# pypl.net
KiCad netlist of a schematic drawn in EAGLE
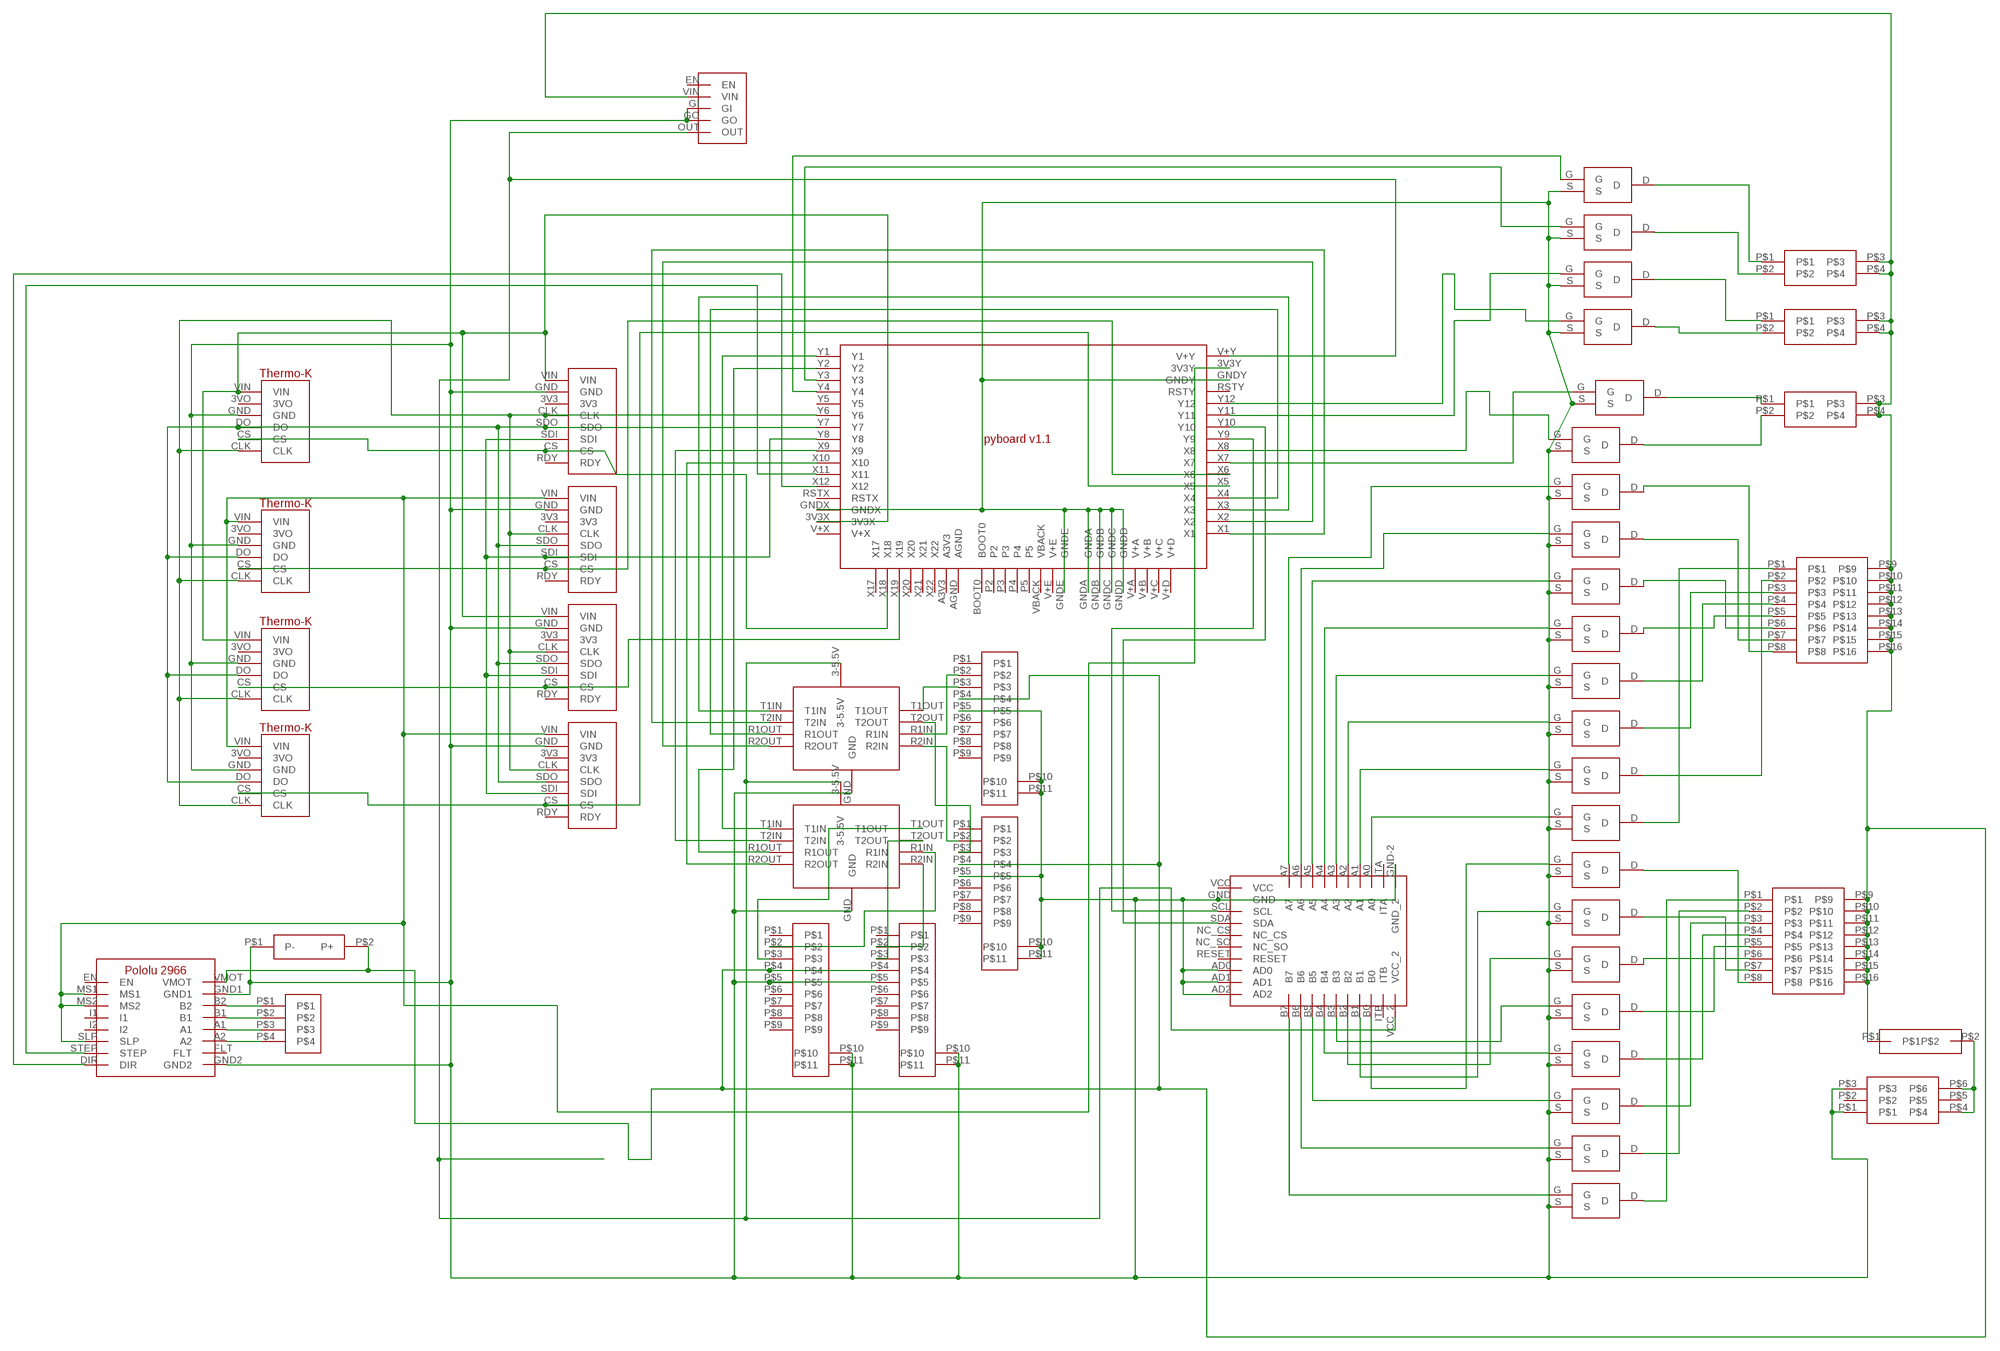
[diagram p0: schematic, sheet 1]

(export (version "E")
  (design (tool "Eeschema 10.0.6"))
  (components
    (comp (ref "U$1")
      (value "MAX31865")
      (footprint "eagle-import:MAX31865")
      (libsource (lib "eagle-import") (part "MAX31865"))
    )
    (comp (ref "U$2")
      (value "IRLB8721PBF")
      (footprint "eagle-import:IRLB8721PBF")
      (libsource (lib "eagle-import") (part "IRLB8721PBF"))
    )
    (comp (ref "U$3")
      (value "IRLB8721PBF")
      (footprint "eagle-import:IRLB8721PBF")
      (libsource (lib "eagle-import") (part "IRLB8721PBF"))
    )
    (comp (ref "U$4")
      (value "IRLB8721PBF")
      (footprint "eagle-import:IRLB8721PBF")
      (libsource (lib "eagle-import") (part "IRLB8721PBF"))
    )
    (comp (ref "U$5")
      (value "IRLB8721PBF")
      (footprint "eagle-import:IRLB8721PBF")
      (libsource (lib "eagle-import") (part "IRLB8721PBF"))
    )
    (comp (ref "U$6")
      (value "IRLB8721PBF")
      (footprint "eagle-import:IRLB8721PBF")
      (libsource (lib "eagle-import") (part "IRLB8721PBF"))
    )
    (comp (ref "U$7")
      (value "IRLB8721PBF")
      (footprint "eagle-import:IRLB8721PBF")
      (libsource (lib "eagle-import") (part "IRLB8721PBF"))
    )
    (comp (ref "U$8")
      (value "IRLB8721PBF")
      (footprint "eagle-import:IRLB8721PBF")
      (libsource (lib "eagle-import") (part "IRLB8721PBF"))
    )
    (comp (ref "U$9")
      (value "IRLB8721PBF")
      (footprint "eagle-import:IRLB8721PBF")
      (libsource (lib "eagle-import") (part "IRLB8721PBF"))
    )
    (comp (ref "U$10")
      (value "MCP23017")
      (footprint "eagle-import:MCP23017")
      (libsource (lib "eagle-import") (part "MCP23017"))
    )
    (comp (ref "U$11")
      (value "IRLB8721PBF")
      (footprint "eagle-import:IRLB8721PBF")
      (libsource (lib "eagle-import") (part "IRLB8721PBF"))
    )
    (comp (ref "U$12")
      (value "IRLB8721PBF")
      (footprint "eagle-import:IRLB8721PBF")
      (libsource (lib "eagle-import") (part "IRLB8721PBF"))
    )
    (comp (ref "U$13")
      (value "IRLB8721PBF")
      (footprint "eagle-import:IRLB8721PBF")
      (libsource (lib "eagle-import") (part "IRLB8721PBF"))
    )
    (comp (ref "U$14")
      (value "IRLB8721PBF")
      (footprint "eagle-import:IRLB8721PBF")
      (libsource (lib "eagle-import") (part "IRLB8721PBF"))
    )
    (comp (ref "U$15")
      (value "IRLB8721PBF")
      (footprint "eagle-import:IRLB8721PBF")
      (libsource (lib "eagle-import") (part "IRLB8721PBF"))
    )
    (comp (ref "U$16")
      (value "IRLB8721PBF")
      (footprint "eagle-import:IRLB8721PBF")
      (libsource (lib "eagle-import") (part "IRLB8721PBF"))
    )
    (comp (ref "U$17")
      (value "IRLB8721PBF")
      (footprint "eagle-import:IRLB8721PBF")
      (libsource (lib "eagle-import") (part "IRLB8721PBF"))
    )
    (comp (ref "U$18")
      (value "IRLB8721PBF")
      (footprint "eagle-import:IRLB8721PBF")
      (libsource (lib "eagle-import") (part "IRLB8721PBF"))
    )
    (comp (ref "U$19")
      (value "DSUB-9")
      (footprint "eagle-import:DSUB-9")
      (libsource (lib "eagle-import") (part "DSUB-9"))
    )
    (comp (ref "U$20")
      (value "DSUB-9")
      (footprint "eagle-import:DSUB-9")
      (libsource (lib "eagle-import") (part "DSUB-9"))
    )
    (comp (ref "U$21")
      (value "DSUB-9")
      (footprint "eagle-import:DSUB-9")
      (libsource (lib "eagle-import") (part "DSUB-9"))
    )
    (comp (ref "U$22")
      (value "DSUB-9")
      (footprint "eagle-import:DSUB-9")
      (libsource (lib "eagle-import") (part "DSUB-9"))
    )
    (comp (ref "U$23")
      (value "MAX31865")
      (footprint "eagle-import:MAX31865")
      (libsource (lib "eagle-import") (part "MAX31865"))
    )
    (comp (ref "U$24")
      (value "PYBOARD_V1.1")
      (footprint "eagle-import:PYBOARD_V1.1")
      (libsource (lib "eagle-import") (part "PYBOARD_V1.1"))
    )
    (comp (ref "U$25")
      (value "MAX31865")
      (footprint "eagle-import:MAX31865")
      (libsource (lib "eagle-import") (part "MAX31865"))
    )
    (comp (ref "U$26")
      (value "MAX31865")
      (footprint "eagle-import:MAX31865")
      (libsource (lib "eagle-import") (part "MAX31865"))
    )
    (comp (ref "U$27")
      (value "BORNIER_DUPLEX_X16")
      (footprint "eagle-import:BORNIER_DUPLEX_X16")
      (libsource (lib "eagle-import") (part "BORNIER_DUPLEX_X16"))
    )
    (comp (ref "U$28")
      (value "BORNIER_DUPLEX_X16")
      (footprint "eagle-import:BORNIER_DUPLEX_X16")
      (libsource (lib "eagle-import") (part "BORNIER_DUPLEX_X16"))
    )
    (comp (ref "U$29")
      (value "CAP-GOTRONIC-04936")
      (footprint "eagle-import:CAP-GOTRONIC-04936")
      (libsource (lib "eagle-import") (part "CAP-GOTRONIC-04936"))
    )
    (comp (ref "U$30")
      (value "BORNIER_1X4_2.54")
      (footprint "eagle-import:BORNIER_1X4_2.54")
      (libsource (lib "eagle-import") (part "BORNIER_1X4_2.54"))
    )
    (comp (ref "U$31")
      (value "PORTE-FUSIBLE")
      (footprint "eagle-import:PORTE-FUSIBLE")
      (libsource (lib "eagle-import") (part "PORTE-FUSIBLE"))
    )
    (comp (ref "U$32")
      (value "MP6500-2966")
      (footprint "eagle-import:MP6500-2966")
      (libsource (lib "eagle-import") (part "MP6500-2966"))
    )
    (comp (ref "U$33")
      (value "IRLB8721PBF")
      (footprint "eagle-import:IRLB8721PBF")
      (libsource (lib "eagle-import") (part "IRLB8721PBF"))
    )
    (comp (ref "U$34")
      (value "IRLB8721PBF")
      (footprint "eagle-import:IRLB8721PBF")
      (libsource (lib "eagle-import") (part "IRLB8721PBF"))
    )
    (comp (ref "U$35")
      (value "BORNIER_DUPLEX_X4")
      (footprint "eagle-import:BORNIER_DUPLEX_X4")
      (libsource (lib "eagle-import") (part "BORNIER_DUPLEX_X4"))
    )
    (comp (ref "U$36")
      (value "BOB-1189")
      (footprint "eagle-import:BOB-11189")
      (libsource (lib "eagle-import") (part "BOB-1189"))
    )
    (comp (ref "U$37")
      (value "BOB-1189")
      (footprint "eagle-import:BOB-11189")
      (libsource (lib "eagle-import") (part "BOB-1189"))
    )
    (comp (ref "U$38")
      (value "MOLEX_MINIFT_JR_ANGLED_X6")
      (footprint "eagle-import:MOLEX_MINIFT_JR_ANGLED_X6")
      (libsource (lib "eagle-import") (part "MOLEX_MINIFT_JR_ANGLED_X6"))
    )
    (comp (ref "U$39")
      (value "D24V50F5D24V50F5")
      (footprint "eagle-import:D24V50F5")
      (libsource (lib "eagle-import") (part "D24V50F5D24V50F5"))
    )
    (comp (ref "U$40")
      (value "BORNIER_DUPLEX_X4")
      (footprint "eagle-import:BORNIER_DUPLEX_X4")
      (libsource (lib "eagle-import") (part "BORNIER_DUPLEX_X4"))
    )
    (comp (ref "U$41")
      (value "BORNIER_DUPLEX_X4")
      (footprint "eagle-import:BORNIER_DUPLEX_X4")
      (libsource (lib "eagle-import") (part "BORNIER_DUPLEX_X4"))
    )
    (comp (ref "U$42")
      (value "IRLB8721PBF")
      (footprint "eagle-import:IRLB8721PBF")
      (libsource (lib "eagle-import") (part "IRLB8721PBF"))
    )
    (comp (ref "U$43")
      (value "IRLB8721PBF")
      (footprint "eagle-import:IRLB8721PBF")
      (libsource (lib "eagle-import") (part "IRLB8721PBF"))
    )
    (comp (ref "U$44")
      (value "IRLB8721PBF")
      (footprint "eagle-import:IRLB8721PBF")
      (libsource (lib "eagle-import") (part "IRLB8721PBF"))
    )
    (comp (ref "U$45")
      (value "IRLB8721PBF")
      (footprint "eagle-import:IRLB8721PBF")
      (libsource (lib "eagle-import") (part "IRLB8721PBF"))
    )
    (comp (ref "U$46")
      (value "MAX31855")
      (footprint "eagle-import:MAX31855")
      (libsource (lib "eagle-import") (part "MAX31855"))
    )
    (comp (ref "U$47")
      (value "MAX31855")
      (footprint "eagle-import:MAX31855")
      (libsource (lib "eagle-import") (part "MAX31855"))
    )
    (comp (ref "U$48")
      (value "MAX31855")
      (footprint "eagle-import:MAX31855")
      (libsource (lib "eagle-import") (part "MAX31855"))
    )
    (comp (ref "U$49")
      (value "MAX31855")
      (footprint "eagle-import:MAX31855")
      (libsource (lib "eagle-import") (part "MAX31855"))
    )
  )
  (nets
    (net (code "1") (name "Net-(U$1-PadCLK)") (class "Default")
      (node (ref "U$1") (pin "CLK") (pinfunction "CLK_CLK") (pintype "bidirectional"))
      (node (ref "U$23") (pin "CLK") (pinfunction "CLK_CLK") (pintype "bidirectional"))
      (node (ref "U$24") (pin "Y6") (pinfunction "Y6_Y6") (pintype "bidirectional"))
      (node (ref "U$25") (pin "CLK") (pinfunction "CLK_CLK") (pintype "bidirectional"))
      (node (ref "U$26") (pin "CLK") (pinfunction "CLK_CLK") (pintype "bidirectional"))
      (node (ref "U$46") (pin "CLK") (pinfunction "CLK_CLK") (pintype "bidirectional"))
      (node (ref "U$47") (pin "CLK") (pinfunction "CLK_CLK") (pintype "bidirectional"))
      (node (ref "U$48") (pin "CLK") (pinfunction "CLK_CLK") (pintype "bidirectional"))
      (node (ref "U$49") (pin "CLK") (pinfunction "CLK_CLK") (pintype "bidirectional"))
    )
    (net (code "2") (name "Net-(U$1-PadCS)") (class "Default")
      (node (ref "U$1") (pin "CS") (pinfunction "CS_CS") (pintype "bidirectional"))
      (node (ref "U$24") (pin "X19") (pinfunction "X19_X19") (pintype "bidirectional"))
      (node (ref "U$48") (pin "CS") (pinfunction "CS_CS") (pintype "bidirectional"))
    )
    (net (code "3") (name "Net-(U$1-PadSDI)") (class "Default")
      (node (ref "U$1") (pin "SDI") (pinfunction "SDI_SDI") (pintype "bidirectional"))
      (node (ref "U$23") (pin "SDI") (pinfunction "SDI_SDI") (pintype "bidirectional"))
      (node (ref "U$24") (pin "Y8") (pinfunction "Y8_Y8") (pintype "bidirectional"))
      (node (ref "U$25") (pin "SDI") (pinfunction "SDI_SDI") (pintype "bidirectional"))
      (node (ref "U$26") (pin "SDI") (pinfunction "SDI_SDI") (pintype "bidirectional"))
    )
    (net (code "4") (name "Net-(U$1-PadSDO)") (class "Default")
      (node (ref "U$1") (pin "SDO") (pinfunction "SDO_SDO") (pintype "bidirectional"))
      (node (ref "U$23") (pin "SDO") (pinfunction "SDO_SDO") (pintype "bidirectional"))
      (node (ref "U$24") (pin "Y7") (pinfunction "Y7_Y7") (pintype "bidirectional"))
      (node (ref "U$25") (pin "SDO") (pinfunction "SDO_SDO") (pintype "bidirectional"))
      (node (ref "U$26") (pin "SDO") (pinfunction "SDO_SDO") (pintype "bidirectional"))
      (node (ref "U$46") (pin "DO") (pinfunction "DO_DO") (pintype "bidirectional"))
      (node (ref "U$47") (pin "DO") (pinfunction "DO_DO") (pintype "bidirectional"))
      (node (ref "U$48") (pin "DO") (pinfunction "DO_DO") (pintype "bidirectional"))
      (node (ref "U$49") (pin "DO") (pinfunction "DO_DO") (pintype "bidirectional"))
    )
    (net (code "5") (name "Net-(U$1-PadVIN)") (class "Default")
      (node (ref "U$1") (pin "VIN") (pinfunction "VIN_VIN") (pintype "bidirectional"))
      (node (ref "U$24") (pin "3V3X") (pinfunction "3V3X_3V3X") (pintype "bidirectional"))
      (node (ref "U$25") (pin "VIN") (pinfunction "VIN_VIN") (pintype "bidirectional"))
      (node (ref "U$46") (pin "VIN") (pinfunction "VIN_VIN") (pintype "bidirectional"))
      (node (ref "U$48") (pin "VIN") (pinfunction "VIN_VIN") (pintype "bidirectional"))
    )
    (net (code "6") (name "Net-(U$2-PadD)") (class "Default")
      (node (ref "U$2") (pin "D") (pinfunction "D_D") (pintype "bidirectional"))
      (node (ref "U$28") (pin "P$3") (pinfunction "P$3_P$3") (pintype "bidirectional"))
    )
    (net (code "7") (name "Net-(U$10-GND_2)") (class "Default")
      (node (ref "U$1") (pin "GND") (pinfunction "GND_GND") (pintype "bidirectional"))
      (node (ref "U$10") (pin "AD0") (pinfunction "AD0_AD0") (pintype "bidirectional"))
      (node (ref "U$10") (pin "AD1") (pinfunction "AD1_AD1") (pintype "bidirectional"))
      (node (ref "U$10") (pin "AD2") (pinfunction "AD2_AD2") (pintype "bidirectional"))
      (node (ref "U$10") (pin "GND") (pinfunction "GND_GND") (pintype "bidirectional"))
      (node (ref "U$10") (pin "GND-2") (pinfunction "GND_2_GND-2") (pintype "bidirectional"))
      (node (ref "U$11") (pin "S") (pinfunction "S_S") (pintype "bidirectional"))
      (node (ref "U$12") (pin "S") (pinfunction "S_S") (pintype "bidirectional"))
      (node (ref "U$13") (pin "S") (pinfunction "S_S") (pintype "bidirectional"))
      (node (ref "U$14") (pin "S") (pinfunction "S_S") (pintype "bidirectional"))
      (node (ref "U$15") (pin "S") (pinfunction "S_S") (pintype "bidirectional"))
      (node (ref "U$16") (pin "S") (pinfunction "S_S") (pintype "bidirectional"))
      (node (ref "U$17") (pin "S") (pinfunction "S_S") (pintype "bidirectional"))
      (node (ref "U$18") (pin "S") (pinfunction "S_S") (pintype "bidirectional"))
      (node (ref "U$19") (pin "P$10") (pinfunction "P$10_P$10") (pintype "bidirectional"))
      (node (ref "U$19") (pin "P$11") (pinfunction "P$11_P$11") (pintype "bidirectional"))
      (node (ref "U$19") (pin "P$5") (pinfunction "P$5_P$5") (pintype "bidirectional"))
      (node (ref "U$2") (pin "S") (pinfunction "S_S") (pintype "bidirectional"))
      (node (ref "U$20") (pin "P$10") (pinfunction "P$10_P$10") (pintype "bidirectional"))
      (node (ref "U$20") (pin "P$11") (pinfunction "P$11_P$11") (pintype "bidirectional"))
      (node (ref "U$20") (pin "P$5") (pinfunction "P$5_P$5") (pintype "bidirectional"))
      (node (ref "U$21") (pin "P$10") (pinfunction "P$10_P$10") (pintype "bidirectional"))
      (node (ref "U$21") (pin "P$11") (pinfunction "P$11_P$11") (pintype "bidirectional"))
      (node (ref "U$21") (pin "P$5") (pinfunction "P$5_P$5") (pintype "bidirectional"))
      (node (ref "U$22") (pin "P$10") (pinfunction "P$10_P$10") (pintype "bidirectional"))
      (node (ref "U$22") (pin "P$11") (pinfunction "P$11_P$11") (pintype "bidirectional"))
      (node (ref "U$22") (pin "P$5") (pinfunction "P$5_P$5") (pintype "bidirectional"))
      (node (ref "U$23") (pin "GND") (pinfunction "GND_GND") (pintype "bidirectional"))
      (node (ref "U$24") (pin "GNDA") (pinfunction "GNDA_GNDA") (pintype "bidirectional"))
      (node (ref "U$24") (pin "GNDB") (pinfunction "GNDB_GNDB") (pintype "bidirectional"))
      (node (ref "U$24") (pin "GNDC") (pinfunction "GNDC_GNDC") (pintype "bidirectional"))
      (node (ref "U$24") (pin "GNDD") (pinfunction "GNDD_GNDD") (pintype "bidirectional"))
      (node (ref "U$24") (pin "GNDE") (pinfunction "GNDE_GNDE") (pintype "bidirectional"))
      (node (ref "U$24") (pin "GNDX") (pinfunction "GNDX_GNDX") (pintype "bidirectional"))
      (node (ref "U$24") (pin "GNDY") (pinfunction "GNDY_GNDY") (pintype "bidirectional"))
      (node (ref "U$25") (pin "GND") (pinfunction "GND_GND") (pintype "bidirectional"))
      (node (ref "U$26") (pin "GND") (pinfunction "GND_GND") (pintype "bidirectional"))
      (node (ref "U$29") (pin "P$1") (pinfunction "P-_P$1") (pintype "bidirectional"))
      (node (ref "U$3") (pin "S") (pinfunction "S_S") (pintype "bidirectional"))
      (node (ref "U$32") (pin "GND1") (pinfunction "GND1_GND1") (pintype "bidirectional"))
      (node (ref "U$32") (pin "GND2") (pinfunction "GND2_GND2") (pintype "bidirectional"))
      (node (ref "U$33") (pin "S") (pinfunction "S_S") (pintype "bidirectional"))
      (node (ref "U$34") (pin "S") (pinfunction "S_S") (pintype "bidirectional"))
      (node (ref "U$36") (pin "GND") (pinfunction "GND_GND") (pintype "bidirectional"))
      (node (ref "U$37") (pin "GND") (pinfunction "GND_GND") (pintype "bidirectional"))
      (node (ref "U$38") (pin "P$1") (pinfunction "P$1_P$1") (pintype "bidirectional"))
      (node (ref "U$38") (pin "P$3") (pinfunction "P$3_P$3") (pintype "bidirectional"))
      (node (ref "U$39") (pin "GI") (pinfunction "GI_GI") (pintype "bidirectional"))
      (node (ref "U$39") (pin "GO") (pinfunction "GO_GO") (pintype "bidirectional"))
      (node (ref "U$4") (pin "S") (pinfunction "S_S") (pintype "bidirectional"))
      (node (ref "U$42") (pin "S") (pinfunction "S_S") (pintype "bidirectional"))
      (node (ref "U$43") (pin "S") (pinfunction "S_S") (pintype "bidirectional"))
      (node (ref "U$44") (pin "S") (pinfunction "S_S") (pintype "bidirectional"))
      (node (ref "U$45") (pin "S") (pinfunction "S_S") (pintype "bidirectional"))
      (node (ref "U$46") (pin "GND") (pinfunction "GND_GND") (pintype "bidirectional"))
      (node (ref "U$47") (pin "GND") (pinfunction "GND_GND") (pintype "bidirectional"))
      (node (ref "U$48") (pin "GND") (pinfunction "GND_GND") (pintype "bidirectional"))
      (node (ref "U$49") (pin "GND") (pinfunction "GND_GND") (pintype "bidirectional"))
      (node (ref "U$5") (pin "S") (pinfunction "S_S") (pintype "bidirectional"))
      (node (ref "U$6") (pin "S") (pinfunction "S_S") (pintype "bidirectional"))
      (node (ref "U$7") (pin "S") (pinfunction "S_S") (pintype "bidirectional"))
      (node (ref "U$8") (pin "S") (pinfunction "S_S") (pintype "bidirectional"))
      (node (ref "U$9") (pin "S") (pinfunction "S_S") (pintype "bidirectional"))
    )
    (net (code "8") (name "Net-(U$10-PadA0)") (class "Default")
      (node (ref "U$10") (pin "A0") (pinfunction "A0_A0") (pintype "bidirectional"))
      (node (ref "U$9") (pin "G") (pinfunction "G_G") (pintype "bidirectional"))
    )
    (net (code "9") (name "Net-(U$10-PadA1)") (class "Default")
      (node (ref "U$10") (pin "A1") (pinfunction "A1_A1") (pintype "bidirectional"))
      (node (ref "U$8") (pin "G") (pinfunction "G_G") (pintype "bidirectional"))
    )
    (net (code "10") (name "Net-(U$10-PadA2)") (class "Default")
      (node (ref "U$10") (pin "A2") (pinfunction "A2_A2") (pintype "bidirectional"))
      (node (ref "U$2") (pin "G") (pinfunction "G_G") (pintype "bidirectional"))
    )
    (net (code "11") (name "Net-(U$10-PadA3)") (class "Default")
      (node (ref "U$10") (pin "A3") (pinfunction "A3_A3") (pintype "bidirectional"))
      (node (ref "U$3") (pin "G") (pinfunction "G_G") (pintype "bidirectional"))
    )
    (net (code "12") (name "Net-(U$10-PadA4)") (class "Default")
      (node (ref "U$10") (pin "A4") (pinfunction "A4_A4") (pintype "bidirectional"))
      (node (ref "U$4") (pin "G") (pinfunction "G_G") (pintype "bidirectional"))
    )
    (net (code "13") (name "Net-(U$10-PadA5)") (class "Default")
      (node (ref "U$10") (pin "A5") (pinfunction "A5_A5") (pintype "bidirectional"))
      (node (ref "U$5") (pin "G") (pinfunction "G_G") (pintype "bidirectional"))
    )
    (net (code "14") (name "Net-(U$10-PadA6)") (class "Default")
      (node (ref "U$10") (pin "A6") (pinfunction "A6_A6") (pintype "bidirectional"))
      (node (ref "U$6") (pin "G") (pinfunction "G_G") (pintype "bidirectional"))
    )
    (net (code "15") (name "Net-(U$10-PadA7)") (class "Default")
      (node (ref "U$10") (pin "A7") (pinfunction "A7_A7") (pintype "bidirectional"))
      (node (ref "U$7") (pin "G") (pinfunction "G_G") (pintype "bidirectional"))
    )
    (net (code "16") (name "Net-(U$10-PadB0)") (class "Default")
      (node (ref "U$10") (pin "B0") (pinfunction "B0_B0") (pintype "bidirectional"))
      (node (ref "U$16") (pin "G") (pinfunction "G_G") (pintype "bidirectional"))
    )
    (net (code "17") (name "Net-(U$10-PadB1)") (class "Default")
      (node (ref "U$10") (pin "B1") (pinfunction "B1_B1") (pintype "bidirectional"))
      (node (ref "U$15") (pin "G") (pinfunction "G_G") (pintype "bidirectional"))
    )
    (net (code "18") (name "Net-(U$10-PadB2)") (class "Default")
      (node (ref "U$10") (pin "B2") (pinfunction "B2_B2") (pintype "bidirectional"))
      (node (ref "U$14") (pin "G") (pinfunction "G_G") (pintype "bidirectional"))
    )
    (net (code "19") (name "Net-(U$10-PadB3)") (class "Default")
      (node (ref "U$10") (pin "B3") (pinfunction "B3_B3") (pintype "bidirectional"))
      (node (ref "U$13") (pin "G") (pinfunction "G_G") (pintype "bidirectional"))
    )
    (net (code "20") (name "Net-(U$10-PadB4)") (class "Default")
      (node (ref "U$10") (pin "B4") (pinfunction "B4_B4") (pintype "bidirectional"))
      (node (ref "U$12") (pin "G") (pinfunction "G_G") (pintype "bidirectional"))
    )
    (net (code "21") (name "Net-(U$10-PadB5)") (class "Default")
      (node (ref "U$10") (pin "B5") (pinfunction "B5_B5") (pintype "bidirectional"))
      (node (ref "U$11") (pin "G") (pinfunction "G_G") (pintype "bidirectional"))
    )
    (net (code "22") (name "Net-(U$10-PadB6)") (class "Default")
      (node (ref "U$10") (pin "B6") (pinfunction "B6_B6") (pintype "bidirectional"))
      (node (ref "U$17") (pin "G") (pinfunction "G_G") (pintype "bidirectional"))
    )
    (net (code "23") (name "Net-(U$10-PadB7)") (class "Default")
      (node (ref "U$10") (pin "B7") (pinfunction "B7_B7") (pintype "bidirectional"))
      (node (ref "U$18") (pin "G") (pinfunction "G_G") (pintype "bidirectional"))
    )
    (net (code "24") (name "Net-(U$10-PadSCL)") (class "Default")
      (node (ref "U$10") (pin "SCL") (pinfunction "SCL_SCL") (pintype "bidirectional"))
      (node (ref "U$24") (pin "Y9") (pinfunction "Y9_Y9") (pintype "bidirectional"))
    )
    (net (code "25") (name "Net-(U$10-PadSDA)") (class "Default")
      (node (ref "U$10") (pin "SDA") (pinfunction "SDA_SDA") (pintype "bidirectional"))
      (node (ref "U$24") (pin "Y10") (pinfunction "Y10_Y10") (pintype "bidirectional"))
    )
    (net (code "26") (name "Net-(U$10-PadVCC_2)") (class "Default")
      (node (ref "U$10") (pin "VCC_2") (pinfunction "VCC_2_VCC_2") (pintype "bidirectional"))
      (node (ref "U$24") (pin "V+Y") (pinfunction "V+Y_V+Y") (pintype "bidirectional"))
      (node (ref "U$36") (pin "3-5.5V") (pinfunction "3-5.5V_3-5.5V") (pintype "bidirectional"))
      (node (ref "U$37") (pin "3-5.5V") (pinfunction "3-5.5V_3-5.5V") (pintype "bidirectional"))
      (node (ref "U$39") (pin "OUT") (pinfunction "OUT_OUT") (pintype "bidirectional"))
    )
    (net (code "27") (name "Net-(U$11-PadD)") (class "Default")
      (node (ref "U$11") (pin "D") (pinfunction "D_D") (pintype "bidirectional"))
      (node (ref "U$27") (pin "P$3") (pinfunction "P$3_P$3") (pintype "bidirectional"))
    )
    (net (code "28") (name "Net-(U$12-PadD)") (class "Default")
      (node (ref "U$12") (pin "D") (pinfunction "D_D") (pintype "bidirectional"))
      (node (ref "U$27") (pin "P$4") (pinfunction "P$4_P$4") (pintype "bidirectional"))
    )
    (net (code "29") (name "Net-(U$13-PadD)") (class "Default")
      (node (ref "U$13") (pin "D") (pinfunction "D_D") (pintype "bidirectional"))
      (node (ref "U$27") (pin "P$5") (pinfunction "P$5_P$5") (pintype "bidirectional"))
    )
    (net (code "30") (name "Net-(U$14-PadD)") (class "Default")
      (node (ref "U$14") (pin "D") (pinfunction "D_D") (pintype "bidirectional"))
      (node (ref "U$27") (pin "P$6") (pinfunction "P$6_P$6") (pintype "bidirectional"))
    )
    (net (code "31") (name "Net-(U$15-PadD)") (class "Default")
      (node (ref "U$15") (pin "D") (pinfunction "D_D") (pintype "bidirectional"))
      (node (ref "U$27") (pin "P$7") (pinfunction "P$7_P$7") (pintype "bidirectional"))
    )
    (net (code "32") (name "Net-(U$16-PadD)") (class "Default")
      (node (ref "U$16") (pin "D") (pinfunction "D_D") (pintype "bidirectional"))
      (node (ref "U$27") (pin "P$8") (pinfunction "P$8_P$8") (pintype "bidirectional"))
    )
    (net (code "33") (name "Net-(U$17-PadD)") (class "Default")
      (node (ref "U$17") (pin "D") (pinfunction "D_D") (pintype "bidirectional"))
      (node (ref "U$27") (pin "P$2") (pinfunction "P$2_P$2") (pintype "bidirectional"))
    )
    (net (code "34") (name "Net-(U$18-PadD)") (class "Default")
      (node (ref "U$18") (pin "D") (pinfunction "D_D") (pintype "bidirectional"))
      (node (ref "U$27") (pin "P$1") (pinfunction "P$1_P$1") (pintype "bidirectional"))
    )
    (net (code "35") (name "Net-(U$19-PadP$2)") (class "Default")
      (node (ref "U$19") (pin "P$2") (pinfunction "P$2_P$2") (pintype "bidirectional"))
      (node (ref "U$36") (pin "R1IN") (pinfunction "R1IN_R1IN") (pintype "bidirectional"))
    )
    (net (code "36") (name "Net-(U$19-PadP$3)") (class "Default")
      (node (ref "U$19") (pin "P$3") (pinfunction "P$3_P$3") (pintype "bidirectional"))
      (node (ref "U$36") (pin "T1OUT") (pinfunction "T1OUT_T1OUT") (pintype "bidirectional"))
    )
    (net (code "37") (name "Net-(U$20-PadP$2)") (class "Default")
      (node (ref "U$20") (pin "P$2") (pinfunction "P$2_P$2") (pintype "bidirectional"))
      (node (ref "U$36") (pin "R2IN") (pinfunction "R2IN_R2IN") (pintype "bidirectional"))
    )
    (net (code "38") (name "Net-(U$20-PadP$3)") (class "Default")
      (node (ref "U$20") (pin "P$3") (pinfunction "P$3_P$3") (pintype "bidirectional"))
      (node (ref "U$36") (pin "T2OUT") (pinfunction "T2OUT_T2OUT") (pintype "bidirectional"))
    )
    (net (code "39") (name "Net-(U$21-PadP$2)") (class "Default")
      (node (ref "U$21") (pin "P$2") (pinfunction "P$2_P$2") (pintype "bidirectional"))
      (node (ref "U$37") (pin "R2IN") (pinfunction "R2IN_R2IN") (pintype "bidirectional"))
    )
    (net (code "40") (name "Net-(U$21-PadP$3)") (class "Default")
      (node (ref "U$21") (pin "P$3") (pinfunction "P$3_P$3") (pintype "bidirectional"))
      (node (ref "U$37") (pin "T2OUT") (pinfunction "T2OUT_T2OUT") (pintype "bidirectional"))
    )
    (net (code "41") (name "Net-(U$22-PadP$2)") (class "Default")
      (node (ref "U$22") (pin "P$2") (pinfunction "P$2_P$2") (pintype "bidirectional"))
      (node (ref "U$37") (pin "R1IN") (pinfunction "R1IN_R1IN") (pintype "bidirectional"))
    )
    (net (code "42") (name "Net-(U$22-PadP$3)") (class "Default")
      (node (ref "U$22") (pin "P$3") (pinfunction "P$3_P$3") (pintype "bidirectional"))
      (node (ref "U$37") (pin "T1OUT") (pinfunction "T1OUT_T1OUT") (pintype "bidirectional"))
    )
    (net (code "43") (name "Net-(U$23-PadCS)") (class "Default")
      (node (ref "U$23") (pin "CS") (pinfunction "CS_CS") (pintype "bidirectional"))
      (node (ref "U$24") (pin "X5") (pinfunction "X5_X5") (pintype "bidirectional"))
      (node (ref "U$49") (pin "CS") (pinfunction "CS_CS") (pintype "bidirectional"))
    )
    (net (code "44") (name "Net-(U$23-PadVIN)") (class "Default")
      (node (ref "U$23") (pin "VIN") (pinfunction "VIN_VIN") (pintype "bidirectional"))
      (node (ref "U$24") (pin "3V3Y") (pinfunction "3V3Y_3V3Y") (pintype "bidirectional"))
      (node (ref "U$26") (pin "VIN") (pinfunction "VIN_VIN") (pintype "bidirectional"))
      (node (ref "U$32") (pin "MS1") (pinfunction "MS1_MS1") (pintype "bidirectional"))
      (node (ref "U$32") (pin "MS2") (pinfunction "MS2_MS2") (pintype "bidirectional"))
      (node (ref "U$32") (pin "SLP") (pinfunction "SLP_SLP") (pintype "bidirectional"))
      (node (ref "U$47") (pin "VIN") (pinfunction "VIN_VIN") (pintype "bidirectional"))
      (node (ref "U$49") (pin "VIN") (pinfunction "VIN_VIN") (pintype "bidirectional"))
    )
    (net (code "45") (name "Net-(U$24-PadX1)") (class "Default")
      (node (ref "U$24") (pin "X1") (pinfunction "X1_X1") (pintype "bidirectional"))
      (node (ref "U$36") (pin "T2IN") (pinfunction "T2IN_T2IN") (pintype "bidirectional"))
    )
    (net (code "46") (name "Net-(U$24-PadX2)") (class "Default")
      (node (ref "U$24") (pin "X2") (pinfunction "X2_X2") (pintype "bidirectional"))
      (node (ref "U$36") (pin "R2OUT") (pinfunction "R2OUT_R2OUT") (pintype "bidirectional"))
    )
    (net (code "47") (name "Net-(U$24-PadX3)") (class "Default")
      (node (ref "U$24") (pin "X3") (pinfunction "X3_X3") (pintype "bidirectional"))
      (node (ref "U$36") (pin "T1IN") (pinfunction "T1IN_T1IN") (pintype "bidirectional"))
    )
    (net (code "48") (name "Net-(U$24-PadX4)") (class "Default")
      (node (ref "U$24") (pin "X4") (pinfunction "X4_X4") (pintype "bidirectional"))
      (node (ref "U$36") (pin "R1OUT") (pinfunction "R1OUT_R1OUT") (pintype "bidirectional"))
    )
    (net (code "49") (name "Net-(U$24-PadX6)") (class "Default")
      (node (ref "U$24") (pin "X6") (pinfunction "X6_X6") (pintype "bidirectional"))
      (node (ref "U$26") (pin "CS") (pinfunction "CS_CS") (pintype "bidirectional"))
      (node (ref "U$47") (pin "CS") (pinfunction "CS_CS") (pintype "bidirectional"))
    )
    (net (code "50") (name "Net-(U$24-PadX7)") (class "Default")
      (node (ref "U$24") (pin "X7") (pinfunction "X7_X7") (pintype "bidirectional"))
      (node (ref "U$34") (pin "G") (pinfunction "G_G") (pintype "bidirectional"))
    )
    (net (code "51") (name "Net-(U$24-PadX8)") (class "Default")
      (node (ref "U$24") (pin "X8") (pinfunction "X8_X8") (pintype "bidirectional"))
      (node (ref "U$33") (pin "G") (pinfunction "G_G") (pintype "bidirectional"))
    )
    (net (code "52") (name "Net-(U$24-PadX9)") (class "Default")
      (node (ref "U$24") (pin "X9") (pinfunction "X9_X9") (pintype "bidirectional"))
      (node (ref "U$37") (pin "T2IN") (pinfunction "T2IN_T2IN") (pintype "bidirectional"))
    )
    (net (code "53") (name "Net-(U$24-PadX10)") (class "Default")
      (node (ref "U$24") (pin "X10") (pinfunction "X10_X10") (pintype "bidirectional"))
      (node (ref "U$37") (pin "R2OUT") (pinfunction "R2OUT_R2OUT") (pintype "bidirectional"))
    )
    (net (code "54") (name "Net-(U$24-PadX11)") (class "Default")
      (node (ref "U$24") (pin "X11") (pinfunction "X11_X11") (pintype "bidirectional"))
      (node (ref "U$32") (pin "STEP") (pinfunction "STEP_STEP") (pintype "bidirectional"))
    )
    (net (code "55") (name "Net-(U$24-PadX12)") (class "Default")
      (node (ref "U$24") (pin "X12") (pinfunction "X12_X12") (pintype "bidirectional"))
      (node (ref "U$32") (pin "DIR") (pinfunction "DIR_DIR") (pintype "bidirectional"))
    )
    (net (code "56") (name "Net-(U$24-PadX18)") (class "Default")
      (node (ref "U$24") (pin "X18") (pinfunction "X18_X18") (pintype "bidirectional"))
      (node (ref "U$25") (pin "CS") (pinfunction "CS_CS") (pintype "bidirectional"))
      (node (ref "U$46") (pin "CS") (pinfunction "CS_CS") (pintype "bidirectional"))
    )
    (net (code "57") (name "Net-(U$24-PadY1)") (class "Default")
      (node (ref "U$24") (pin "Y1") (pinfunction "Y1_Y1") (pintype "bidirectional"))
      (node (ref "U$37") (pin "T1IN") (pinfunction "T1IN_T1IN") (pintype "bidirectional"))
    )
    (net (code "58") (name "Net-(U$24-PadY2)") (class "Default")
      (node (ref "U$24") (pin "Y2") (pinfunction "Y2_Y2") (pintype "bidirectional"))
      (node (ref "U$37") (pin "R1OUT") (pinfunction "R1OUT_R1OUT") (pintype "bidirectional"))
    )
    (net (code "59") (name "Net-(U$24-PadY3)") (class "Default")
      (node (ref "U$24") (pin "Y3") (pinfunction "Y3_Y3") (pintype "bidirectional"))
      (node (ref "U$44") (pin "G") (pinfunction "G_G") (pintype "bidirectional"))
    )
    (net (code "60") (name "Net-(U$24-PadY4)") (class "Default")
      (node (ref "U$24") (pin "Y4") (pinfunction "Y4_Y4") (pintype "bidirectional"))
      (node (ref "U$45") (pin "G") (pinfunction "G_G") (pintype "bidirectional"))
    )
    (net (code "61") (name "Net-(U$24-PadY11)") (class "Default")
      (node (ref "U$24") (pin "Y11") (pinfunction "Y11_Y11") (pintype "bidirectional"))
      (node (ref "U$43") (pin "G") (pinfunction "G_G") (pintype "bidirectional"))
    )
    (net (code "62") (name "Net-(U$24-PadY12)") (class "Default")
      (node (ref "U$24") (pin "Y12") (pinfunction "Y12_Y12") (pintype "bidirectional"))
      (node (ref "U$42") (pin "G") (pinfunction "G_G") (pintype "bidirectional"))
    )
    (net (code "63") (name "Net-(U$28-PadP$1)") (class "Default")
      (node (ref "U$28") (pin "P$1") (pinfunction "P$1_P$1") (pintype "bidirectional"))
      (node (ref "U$9") (pin "D") (pinfunction "D_D") (pintype "bidirectional"))
    )
    (net (code "64") (name "Net-(U$28-PadP$2)") (class "Default")
      (node (ref "U$28") (pin "P$2") (pinfunction "P$2_P$2") (pintype "bidirectional"))
      (node (ref "U$8") (pin "D") (pinfunction "D_D") (pintype "bidirectional"))
    )
    (net (code "65") (name "Net-(U$28-PadP$4)") (class "Default")
      (node (ref "U$28") (pin "P$4") (pinfunction "P$4_P$4") (pintype "bidirectional"))
      (node (ref "U$3") (pin "D") (pinfunction "D_D") (pintype "bidirectional"))
    )
    (net (code "66") (name "Net-(U$28-PadP$5)") (class "Default")
      (node (ref "U$28") (pin "P$5") (pinfunction "P$5_P$5") (pintype "bidirectional"))
      (node (ref "U$4") (pin "D") (pinfunction "D_D") (pintype "bidirectional"))
    )
    (net (code "67") (name "Net-(U$28-PadP$6)") (class "Default")
      (node (ref "U$28") (pin "P$6") (pinfunction "P$6_P$6") (pintype "bidirectional"))
      (node (ref "U$5") (pin "D") (pinfunction "D_D") (pintype "bidirectional"))
    )
    (net (code "68") (name "Net-(U$28-PadP$7)") (class "Default")
      (node (ref "U$28") (pin "P$7") (pinfunction "P$7_P$7") (pintype "bidirectional"))
      (node (ref "U$6") (pin "D") (pinfunction "D_D") (pintype "bidirectional"))
    )
    (net (code "69") (name "Net-(U$28-PadP$8)") (class "Default")
      (node (ref "U$28") (pin "P$8") (pinfunction "P$8_P$8") (pintype "bidirectional"))
      (node (ref "U$7") (pin "D") (pinfunction "D_D") (pintype "bidirectional"))
    )
    (net (code "70") (name "Net-(U$29-P+)") (class "Default")
      (node (ref "U$19") (pin "P$4") (pinfunction "P$4_P$4") (pintype "bidirectional"))
      (node (ref "U$20") (pin "P$4") (pinfunction "P$4_P$4") (pintype "bidirectional"))
      (node (ref "U$21") (pin "P$4") (pinfunction "P$4_P$4") (pintype "bidirectional"))
      (node (ref "U$22") (pin "P$4") (pinfunction "P$4_P$4") (pintype "bidirectional"))
      (node (ref "U$27") (pin "P$10") (pinfunction "P$10_P$10") (pintype "bidirectional"))
      (node (ref "U$27") (pin "P$11") (pinfunction "P$11_P$11") (pintype "bidirectional"))
      (node (ref "U$27") (pin "P$12") (pinfunction "P$12_P$12") (pintype "bidirectional"))
      (node (ref "U$27") (pin "P$13") (pinfunction "P$13_P$13") (pintype "bidirectional"))
      (node (ref "U$27") (pin "P$14") (pinfunction "P$14_P$14") (pintype "bidirectional"))
      (node (ref "U$27") (pin "P$15") (pinfunction "P$15_P$15") (pintype "bidirectional"))
      (node (ref "U$27") (pin "P$16") (pinfunction "P$16_P$16") (pintype "bidirectional"))
      (node (ref "U$27") (pin "P$9") (pinfunction "P$9_P$9") (pintype "bidirectional"))
      (node (ref "U$28") (pin "P$10") (pinfunction "P$10_P$10") (pintype "bidirectional"))
      (node (ref "U$28") (pin "P$11") (pinfunction "P$11_P$11") (pintype "bidirectional"))
      (node (ref "U$28") (pin "P$12") (pinfunction "P$12_P$12") (pintype "bidirectional"))
      (node (ref "U$28") (pin "P$13") (pinfunction "P$13_P$13") (pintype "bidirectional"))
      (node (ref "U$28") (pin "P$14") (pinfunction "P$14_P$14") (pintype "bidirectional"))
      (node (ref "U$28") (pin "P$15") (pinfunction "P$15_P$15") (pintype "bidirectional"))
      (node (ref "U$28") (pin "P$16") (pinfunction "P$16_P$16") (pintype "bidirectional"))
      (node (ref "U$28") (pin "P$9") (pinfunction "P$9_P$9") (pintype "bidirectional"))
      (node (ref "U$29") (pin "P$2") (pinfunction "P+_P$2") (pintype "bidirectional"))
      (node (ref "U$31") (pin "P$1") (pinfunction "P$1_P$1") (pintype "bidirectional"))
      (node (ref "U$32") (pin "VMOT") (pinfunction "VMOT_VMOT") (pintype "bidirectional"))
      (node (ref "U$35") (pin "P$3") (pinfunction "P$3_P$3") (pintype "bidirectional"))
      (node (ref "U$35") (pin "P$4") (pinfunction "P$4_P$4") (pintype "bidirectional"))
      (node (ref "U$39") (pin "VIN") (pinfunction "VIN_VIN") (pintype "bidirectional"))
      (node (ref "U$40") (pin "P$3") (pinfunction "P$3_P$3") (pintype "bidirectional"))
      (node (ref "U$40") (pin "P$4") (pinfunction "P$4_P$4") (pintype "bidirectional"))
      (node (ref "U$41") (pin "P$3") (pinfunction "P$3_P$3") (pintype "bidirectional"))
      (node (ref "U$41") (pin "P$4") (pinfunction "P$4_P$4") (pintype "bidirectional"))
    )
    (net (code "71") (name "Net-(U$30-PadP$1)") (class "Default")
      (node (ref "U$30") (pin "P$1") (pinfunction "P$1_P$1") (pintype "bidirectional"))
      (node (ref "U$32") (pin "B2") (pinfunction "B2_B2") (pintype "bidirectional"))
    )
    (net (code "72") (name "Net-(U$30-PadP$2)") (class "Default")
      (node (ref "U$30") (pin "P$2") (pinfunction "P$2_P$2") (pintype "bidirectional"))
      (node (ref "U$32") (pin "B1") (pinfunction "B1_B1") (pintype "bidirectional"))
    )
    (net (code "73") (name "Net-(U$30-PadP$3)") (class "Default")
      (node (ref "U$30") (pin "P$3") (pinfunction "P$3_P$3") (pintype "bidirectional"))
      (node (ref "U$32") (pin "A1") (pinfunction "A1_A1") (pintype "bidirectional"))
    )
    (net (code "74") (name "Net-(U$30-PadP$4)") (class "Default")
      (node (ref "U$30") (pin "P$4") (pinfunction "P$4_P$4") (pintype "bidirectional"))
      (node (ref "U$32") (pin "A2") (pinfunction "A2_A2") (pintype "bidirectional"))
    )
    (net (code "75") (name "Net-(U$31-PadP$2)") (class "Default")
      (node (ref "U$31") (pin "P$2") (pinfunction "P$2_P$2") (pintype "bidirectional"))
      (node (ref "U$38") (pin "P$4") (pinfunction "P$4_P$4") (pintype "bidirectional"))
      (node (ref "U$38") (pin "P$6") (pinfunction "P$6_P$6") (pintype "bidirectional"))
    )
    (net (code "76") (name "Net-(U$33-PadD)") (class "Default")
      (node (ref "U$33") (pin "D") (pinfunction "D_D") (pintype "bidirectional"))
      (node (ref "U$35") (pin "P$2") (pinfunction "P$2_P$2") (pintype "bidirectional"))
    )
    (net (code "77") (name "Net-(U$34-PadD)") (class "Default")
      (node (ref "U$34") (pin "D") (pinfunction "D_D") (pintype "bidirectional"))
      (node (ref "U$35") (pin "P$1") (pinfunction "P$1_P$1") (pintype "bidirectional"))
    )
    (net (code "78") (name "Net-(U$40-PadP$1)") (class "Default")
      (node (ref "U$40") (pin "P$1") (pinfunction "P$1_P$1") (pintype "bidirectional"))
      (node (ref "U$43") (pin "D") (pinfunction "D_D") (pintype "bidirectional"))
    )
    (net (code "79") (name "Net-(U$40-PadP$2)") (class "Default")
      (node (ref "U$40") (pin "P$2") (pinfunction "P$2_P$2") (pintype "bidirectional"))
      (node (ref "U$42") (pin "D") (pinfunction "D_D") (pintype "bidirectional"))
    )
    (net (code "80") (name "Net-(U$41-PadP$1)") (class "Default")
      (node (ref "U$41") (pin "P$1") (pinfunction "P$1_P$1") (pintype "bidirectional"))
      (node (ref "U$45") (pin "D") (pinfunction "D_D") (pintype "bidirectional"))
    )
    (net (code "81") (name "Net-(U$41-PadP$2)") (class "Default")
      (node (ref "U$41") (pin "P$2") (pinfunction "P$2_P$2") (pintype "bidirectional"))
      (node (ref "U$44") (pin "D") (pinfunction "D_D") (pintype "bidirectional"))
    )
    (net (code "82") (name "unconnected-(U$1-Pad3V3)") (class "Default")
      (node (ref "U$1") (pin "3V3") (pinfunction "3V3_3V3") (pintype "bidirectional"))
    )
    (net (code "83") (name "unconnected-(U$1-PadRDY)") (class "Default")
      (node (ref "U$1") (pin "RDY") (pinfunction "RDY_RDY") (pintype "bidirectional"))
    )
    (net (code "84") (name "unconnected-(U$10-PadITA)") (class "Default")
      (node (ref "U$10") (pin "ITA") (pinfunction "ITA_ITA") (pintype "bidirectional"))
    )
    (net (code "85") (name "unconnected-(U$10-PadITB)") (class "Default")
      (node (ref "U$10") (pin "ITB") (pinfunction "ITB_ITB") (pintype "bidirectional"))
    )
    (net (code "86") (name "unconnected-(U$10-PadNC_CS)") (class "Default")
      (node (ref "U$10") (pin "NC_CS") (pinfunction "NC_CS_NC_CS") (pintype "bidirectional"))
    )
    (net (code "87") (name "unconnected-(U$10-PadNC_SO)") (class "Default")
      (node (ref "U$10") (pin "NC_SO") (pinfunction "NC_SO_NC_SO") (pintype "bidirectional"))
    )
    (net (code "88") (name "unconnected-(U$10-PadRESET)") (class "Default")
      (node (ref "U$10") (pin "RESET") (pinfunction "RESET_RESET") (pintype "bidirectional"))
    )
    (net (code "89") (name "unconnected-(U$10-PadVCC)") (class "Default")
      (node (ref "U$10") (pin "VCC") (pinfunction "VCC_VCC") (pintype "bidirectional"))
    )
    (net (code "90") (name "unconnected-(U$19-PadP$1)") (class "Default")
      (node (ref "U$19") (pin "P$1") (pinfunction "P$1_P$1") (pintype "bidirectional"))
    )
    (net (code "91") (name "unconnected-(U$19-PadP$6)") (class "Default")
      (node (ref "U$19") (pin "P$6") (pinfunction "P$6_P$6") (pintype "bidirectional"))
    )
    (net (code "92") (name "unconnected-(U$19-PadP$7)") (class "Default")
      (node (ref "U$19") (pin "P$7") (pinfunction "P$7_P$7") (pintype "bidirectional"))
    )
    (net (code "93") (name "unconnected-(U$19-PadP$8)") (class "Default")
      (node (ref "U$19") (pin "P$8") (pinfunction "P$8_P$8") (pintype "bidirectional"))
    )
    (net (code "94") (name "unconnected-(U$19-PadP$9)") (class "Default")
      (node (ref "U$19") (pin "P$9") (pinfunction "P$9_P$9") (pintype "bidirectional"))
    )
    (net (code "95") (name "unconnected-(U$20-PadP$1)") (class "Default")
      (node (ref "U$20") (pin "P$1") (pinfunction "P$1_P$1") (pintype "bidirectional"))
    )
    (net (code "96") (name "unconnected-(U$20-PadP$6)") (class "Default")
      (node (ref "U$20") (pin "P$6") (pinfunction "P$6_P$6") (pintype "bidirectional"))
    )
    (net (code "97") (name "unconnected-(U$20-PadP$7)") (class "Default")
      (node (ref "U$20") (pin "P$7") (pinfunction "P$7_P$7") (pintype "bidirectional"))
    )
    (net (code "98") (name "unconnected-(U$20-PadP$8)") (class "Default")
      (node (ref "U$20") (pin "P$8") (pinfunction "P$8_P$8") (pintype "bidirectional"))
    )
    (net (code "99") (name "unconnected-(U$20-PadP$9)") (class "Default")
      (node (ref "U$20") (pin "P$9") (pinfunction "P$9_P$9") (pintype "bidirectional"))
    )
    (net (code "100") (name "unconnected-(U$21-PadP$1)") (class "Default")
      (node (ref "U$21") (pin "P$1") (pinfunction "P$1_P$1") (pintype "bidirectional"))
    )
    (net (code "101") (name "unconnected-(U$21-PadP$6)") (class "Default")
      (node (ref "U$21") (pin "P$6") (pinfunction "P$6_P$6") (pintype "bidirectional"))
    )
    (net (code "102") (name "unconnected-(U$21-PadP$7)") (class "Default")
      (node (ref "U$21") (pin "P$7") (pinfunction "P$7_P$7") (pintype "bidirectional"))
    )
    (net (code "103") (name "unconnected-(U$21-PadP$8)") (class "Default")
      (node (ref "U$21") (pin "P$8") (pinfunction "P$8_P$8") (pintype "bidirectional"))
    )
    (net (code "104") (name "unconnected-(U$21-PadP$9)") (class "Default")
      (node (ref "U$21") (pin "P$9") (pinfunction "P$9_P$9") (pintype "bidirectional"))
    )
    (net (code "105") (name "unconnected-(U$22-PadP$1)") (class "Default")
      (node (ref "U$22") (pin "P$1") (pinfunction "P$1_P$1") (pintype "bidirectional"))
    )
    (net (code "106") (name "unconnected-(U$22-PadP$6)") (class "Default")
      (node (ref "U$22") (pin "P$6") (pinfunction "P$6_P$6") (pintype "bidirectional"))
    )
    (net (code "107") (name "unconnected-(U$22-PadP$7)") (class "Default")
      (node (ref "U$22") (pin "P$7") (pinfunction "P$7_P$7") (pintype "bidirectional"))
    )
    (net (code "108") (name "unconnected-(U$22-PadP$8)") (class "Default")
      (node (ref "U$22") (pin "P$8") (pinfunction "P$8_P$8") (pintype "bidirectional"))
    )
    (net (code "109") (name "unconnected-(U$22-PadP$9)") (class "Default")
      (node (ref "U$22") (pin "P$9") (pinfunction "P$9_P$9") (pintype "bidirectional"))
    )
    (net (code "110") (name "unconnected-(U$23-Pad3V3)") (class "Default")
      (node (ref "U$23") (pin "3V3") (pinfunction "3V3_3V3") (pintype "bidirectional"))
    )
    (net (code "111") (name "unconnected-(U$23-PadRDY)") (class "Default")
      (node (ref "U$23") (pin "RDY") (pinfunction "RDY_RDY") (pintype "bidirectional"))
    )
    (net (code "112") (name "unconnected-(U$24-PadA3V3)") (class "Default")
      (node (ref "U$24") (pin "A3V3") (pinfunction "A3V3_A3V3") (pintype "bidirectional"))
    )
    (net (code "113") (name "unconnected-(U$24-PadAGND)") (class "Default")
      (node (ref "U$24") (pin "AGND") (pinfunction "AGND_AGND") (pintype "bidirectional"))
    )
    (net (code "114") (name "unconnected-(U$24-PadBOOT0)") (class "Default")
      (node (ref "U$24") (pin "BOOT0") (pinfunction "BOOT0_BOOT0") (pintype "bidirectional"))
    )
    (net (code "115") (name "unconnected-(U$24-PadP2)") (class "Default")
      (node (ref "U$24") (pin "P2") (pinfunction "P2_P2") (pintype "bidirectional"))
    )
    (net (code "116") (name "unconnected-(U$24-PadP3)") (class "Default")
      (node (ref "U$24") (pin "P3") (pinfunction "P3_P3") (pintype "bidirectional"))
    )
    (net (code "117") (name "unconnected-(U$24-PadP4)") (class "Default")
      (node (ref "U$24") (pin "P4") (pinfunction "P4_P4") (pintype "bidirectional"))
    )
    (net (code "118") (name "unconnected-(U$24-PadP5)") (class "Default")
      (node (ref "U$24") (pin "P5") (pinfunction "P5_P5") (pintype "bidirectional"))
    )
    (net (code "119") (name "unconnected-(U$24-PadRSTX)") (class "Default")
      (node (ref "U$24") (pin "RSTX") (pinfunction "RSTX_RSTX") (pintype "bidirectional"))
    )
    (net (code "120") (name "unconnected-(U$24-PadRSTY)") (class "Default")
      (node (ref "U$24") (pin "RSTY") (pinfunction "RSTY_RSTY") (pintype "bidirectional"))
    )
    (net (code "121") (name "unconnected-(U$24-PadV+A)") (class "Default")
      (node (ref "U$24") (pin "V+A") (pinfunction "V+A_V+A") (pintype "bidirectional"))
    )
    (net (code "122") (name "unconnected-(U$24-PadV+B)") (class "Default")
      (node (ref "U$24") (pin "V+B") (pinfunction "V+B_V+B") (pintype "bidirectional"))
    )
    (net (code "123") (name "unconnected-(U$24-PadV+C)") (class "Default")
      (node (ref "U$24") (pin "V+C") (pinfunction "V+C_V+C") (pintype "bidirectional"))
    )
    (net (code "124") (name "unconnected-(U$24-PadV+D)") (class "Default")
      (node (ref "U$24") (pin "V+D") (pinfunction "V+D_V+D") (pintype "bidirectional"))
    )
    (net (code "125") (name "unconnected-(U$24-PadV+E)") (class "Default")
      (node (ref "U$24") (pin "V+E") (pinfunction "V+E_V+E") (pintype "bidirectional"))
    )
    (net (code "126") (name "unconnected-(U$24-PadV+X)") (class "Default")
      (node (ref "U$24") (pin "V+X") (pinfunction "V+X_V+X") (pintype "bidirectional"))
    )
    (net (code "127") (name "unconnected-(U$24-PadVBACK)") (class "Default")
      (node (ref "U$24") (pin "VBACK") (pinfunction "VBACK_VBACK") (pintype "bidirectional"))
    )
    (net (code "128") (name "unconnected-(U$24-PadX17)") (class "Default")
      (node (ref "U$24") (pin "X17") (pinfunction "X17_X17") (pintype "bidirectional"))
    )
    (net (code "129") (name "unconnected-(U$24-PadX20)") (class "Default")
      (node (ref "U$24") (pin "X20") (pinfunction "X20_X20") (pintype "bidirectional"))
    )
    (net (code "130") (name "unconnected-(U$24-PadX21)") (class "Default")
      (node (ref "U$24") (pin "X21") (pinfunction "X21_X21") (pintype "bidirectional"))
    )
    (net (code "131") (name "unconnected-(U$24-PadX22)") (class "Default")
      (node (ref "U$24") (pin "X22") (pinfunction "X22_X22") (pintype "bidirectional"))
    )
    (net (code "132") (name "unconnected-(U$24-PadY5)") (class "Default")
      (node (ref "U$24") (pin "Y5") (pinfunction "Y5_Y5") (pintype "bidirectional"))
    )
    (net (code "133") (name "unconnected-(U$25-Pad3V3)") (class "Default")
      (node (ref "U$25") (pin "3V3") (pinfunction "3V3_3V3") (pintype "bidirectional"))
    )
    (net (code "134") (name "unconnected-(U$25-PadRDY)") (class "Default")
      (node (ref "U$25") (pin "RDY") (pinfunction "RDY_RDY") (pintype "bidirectional"))
    )
    (net (code "135") (name "unconnected-(U$26-Pad3V3)") (class "Default")
      (node (ref "U$26") (pin "3V3") (pinfunction "3V3_3V3") (pintype "bidirectional"))
    )
    (net (code "136") (name "unconnected-(U$26-PadRDY)") (class "Default")
      (node (ref "U$26") (pin "RDY") (pinfunction "RDY_RDY") (pintype "bidirectional"))
    )
    (net (code "137") (name "unconnected-(U$32-PadEN)") (class "Default")
      (node (ref "U$32") (pin "EN") (pinfunction "EN_EN") (pintype "bidirectional"))
    )
    (net (code "138") (name "unconnected-(U$32-PadFLT)") (class "Default")
      (node (ref "U$32") (pin "FLT") (pinfunction "FLT_FLT") (pintype "bidirectional"))
    )
    (net (code "139") (name "unconnected-(U$32-PadI1)") (class "Default")
      (node (ref "U$32") (pin "I1") (pinfunction "I1_I1") (pintype "bidirectional"))
    )
    (net (code "140") (name "unconnected-(U$32-PadI2)") (class "Default")
      (node (ref "U$32") (pin "I2") (pinfunction "I2_I2") (pintype "bidirectional"))
    )
    (net (code "141") (name "unconnected-(U$38-PadP$2)") (class "Default")
      (node (ref "U$38") (pin "P$2") (pinfunction "P$2_P$2") (pintype "bidirectional"))
    )
    (net (code "142") (name "unconnected-(U$38-PadP$5)") (class "Default")
      (node (ref "U$38") (pin "P$5") (pinfunction "P$5_P$5") (pintype "bidirectional"))
    )
    (net (code "143") (name "unconnected-(U$39-PadEN)") (class "Default")
      (node (ref "U$39") (pin "EN") (pinfunction "EN_EN") (pintype "bidirectional"))
    )
    (net (code "144") (name "unconnected-(U$46-Pad3VO)") (class "Default")
      (node (ref "U$46") (pin "3VO") (pinfunction "3VO_3VO") (pintype "bidirectional"))
    )
    (net (code "145") (name "unconnected-(U$47-Pad3VO)") (class "Default")
      (node (ref "U$47") (pin "3VO") (pinfunction "3VO_3VO") (pintype "bidirectional"))
    )
    (net (code "146") (name "unconnected-(U$48-Pad3VO)") (class "Default")
      (node (ref "U$48") (pin "3VO") (pinfunction "3VO_3VO") (pintype "bidirectional"))
    )
    (net (code "147") (name "unconnected-(U$49-Pad3VO)") (class "Default")
      (node (ref "U$49") (pin "3VO") (pinfunction "3VO_3VO") (pintype "bidirectional"))
    )
  )
)
